# Breakout.net
KiCad netlist of a schematic drawn in Altium Designer
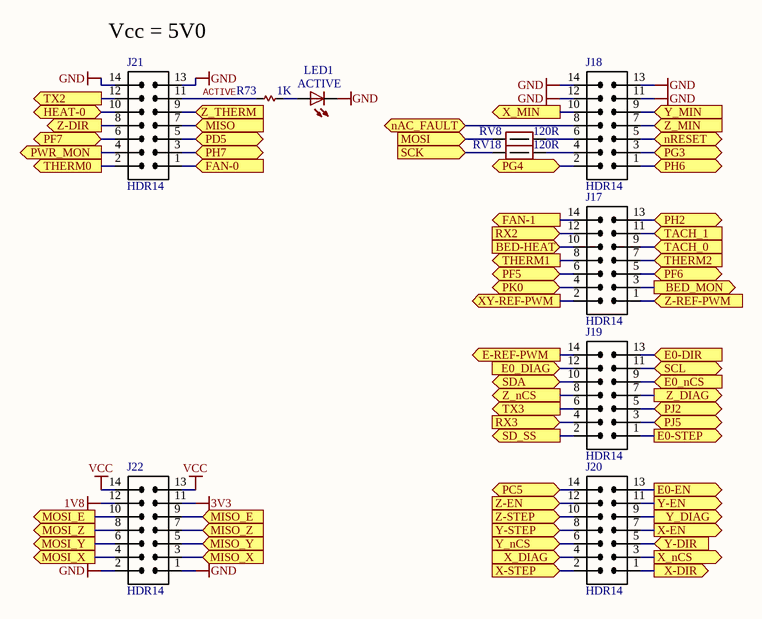
[diagram p0: Breakout.SchDoc]

(export (version "E")
  (design (tool "Eeschema 10.0.6"))
  (components
    (comp (ref "J17")
      (value "HDR14")
      (footprint "HDR2x7_SMT_BOT_ENTRY_EX")
      (description "CONN RCPT DUAL ENTRY 14POS .100\"")
      (fields (field (name "MANUFACTURER") "TE Connectivity") (field (name "TOLERANCE") "-NA-"))
      (libsource (lib "Connectors") (part "CONN 14PIN 0.1{dblquote} FEMALE 2-ROW SMT BOT-ENTRY_EX"))
    )
    (comp (ref "J18")
      (value "HDR14")
      (footprint "HDR2x7_SMT_BOT_ENTRY_EX")
      (description "CONN RCPT DUAL ENTRY 14POS .100\"")
      (fields (field (name "MANUFACTURER") "TE Connectivity") (field (name "TOLERANCE") "-NA-"))
      (libsource (lib "Connectors") (part "CONN 14PIN 0.1{dblquote} FEMALE 2-ROW SMT BOT-ENTRY_EX"))
    )
    (comp (ref "J19")
      (value "HDR14")
      (footprint "HDR2x7_SMT_BOT_ENTRY_EX")
      (description "CONN RCPT DUAL ENTRY 14POS .100\"")
      (fields (field (name "MANUFACTURER") "TE Connectivity") (field (name "TOLERANCE") "-NA-"))
      (libsource (lib "Connectors") (part "CONN 14PIN 0.1{dblquote} FEMALE 2-ROW SMT BOT-ENTRY_EX"))
    )
    (comp (ref "J20")
      (value "HDR14")
      (footprint "HDR2x7_SMT_BOT_ENTRY_EX")
      (description "CONN RCPT DUAL ENTRY 14POS .100\"")
      (fields (field (name "MANUFACTURER") "TE Connectivity") (field (name "TOLERANCE") "-NA-"))
      (libsource (lib "Connectors") (part "CONN 14PIN 0.1{dblquote} FEMALE 2-ROW SMT BOT-ENTRY_EX"))
    )
    (comp (ref "J21")
      (value "HDR14")
      (footprint "HDR2x7_SMT_BOT_ENTRY_EX")
      (description "CONN RCPT DUAL ENTRY 14POS .100\"")
      (fields (field (name "MANUFACTURER") "TE Connectivity") (field (name "TOLERANCE") "-NA-"))
      (libsource (lib "Connectors") (part "CONN 14PIN 0.1{dblquote} FEMALE 2-ROW SMT BOT-ENTRY_EX"))
    )
    (comp (ref "J22")
      (value "HDR14")
      (footprint "HDR2x7_SMT_BOT_ENTRY_EX")
      (description "CONN RCPT DUAL ENTRY 14POS .100\"")
      (fields (field (name "MANUFACTURER") "TE Connectivity") (field (name "TOLERANCE") "-NA-"))
      (libsource (lib "Connectors") (part "CONN 14PIN 0.1{dblquote} FEMALE 2-ROW SMT BOT-ENTRY_EX"))
    )
    (comp (ref "LED1")
      (value "YEL")
      (footprint "LED2012120")
      (description "LED 0805 Yellow")
      (fields (field (name "MANUFACTURER") "Dialight") (field (name "TOLERANCE") "NA"))
      (libsource (lib "3Delight") (part "5988140107F"))
    )
    (comp (ref "R73")
      (value "1K")
      (footprint "R0402")
      (description "RES SMD 1K OHM 1% 1/16W 0402")
      (fields (field (name "MANUFACTURER") "Yageo") (field (name "PART") "1k"))
      (libsource (lib "3Delight") (part "RC0402FR-071KL"))
    )
    (comp (ref "RV8")
      (value "120R")
      (footprint "R0402")
      (description "FERRITE BEAD 120 OHM 0402 1LN")
      (fields (field (name "MANUFACTURER") "Taiyo Yuden") (field (name "PART") "FERRITE 120R 1A 0402"))
      (libsource (lib "Inductors") (part "FERRITE 120R 1A 0402"))
    )
    (comp (ref "RV18")
      (value "120R")
      (footprint "R0402")
      (description "FERRITE BEAD 120 OHM 0402 1LN")
      (fields (field (name "MANUFACTURER") "Taiyo Yuden") (field (name "PART") "FERRITE 120R 1A 0402"))
      (libsource (lib "Inductors") (part "FERRITE 120R 1A 0402"))
    )
  )
  (nets
    (net (code "1") (name "/ACTIVE") (class "Default")
      (node (ref "J21") (pin "11") (pinfunction "S_11") (pintype "passive"))
      (node (ref "R73") (pin "2") (pinfunction "2_2") (pintype "passive"))
    )
    (net (code "2") (name "/BED-HEAT") (class "Default")
      (node (ref "J17") (pin "10") (pinfunction "S_10") (pintype "passive"))
    )
    (net (code "3") (name "/BED_MON") (class "Default")
      (node (ref "J17") (pin "3") (pinfunction "S_3") (pintype "passive"))
    )
    (net (code "4") (name "/E-REF-PWM") (class "Default")
      (node (ref "J19") (pin "14") (pinfunction "S_14") (pintype "passive"))
    )
    (net (code "5") (name "/E0-DIR") (class "Default")
      (node (ref "J19") (pin "13") (pinfunction "S_13") (pintype "passive"))
    )
    (net (code "6") (name "/E0-EN") (class "Default")
      (node (ref "J20") (pin "13") (pinfunction "S_13") (pintype "passive"))
    )
    (net (code "7") (name "/E0-STEP") (class "Default")
      (node (ref "J19") (pin "1") (pinfunction "S_1") (pintype "passive"))
    )
    (net (code "8") (name "/E0_DIAG") (class "Default")
      (node (ref "J19") (pin "12") (pinfunction "S_12") (pintype "passive"))
    )
    (net (code "9") (name "/E0_nCS") (class "Default")
      (node (ref "J19") (pin "9") (pinfunction "S_9") (pintype "passive"))
    )
    (net (code "10") (name "/FAN-0") (class "Default")
      (node (ref "J21") (pin "1") (pinfunction "S_1") (pintype "passive"))
    )
    (net (code "11") (name "/FAN-1") (class "Default")
      (node (ref "J17") (pin "14") (pinfunction "S_14") (pintype "passive"))
    )
    (net (code "12") (name "/HEAT-0") (class "Default")
      (node (ref "J21") (pin "10") (pinfunction "S_10") (pintype "passive"))
    )
    (net (code "13") (name "/MISO") (class "Default")
      (node (ref "J21") (pin "7") (pinfunction "S_7") (pintype "passive"))
    )
    (net (code "14") (name "/MISO_E") (class "Default")
      (node (ref "J22") (pin "9") (pinfunction "S_9") (pintype "passive"))
    )
    (net (code "15") (name "/MISO_X") (class "Default")
      (node (ref "J22") (pin "3") (pinfunction "S_3") (pintype "passive"))
    )
    (net (code "16") (name "/MISO_Y") (class "Default")
      (node (ref "J22") (pin "5") (pinfunction "S_5") (pintype "passive"))
    )
    (net (code "17") (name "/MISO_Z") (class "Default")
      (node (ref "J22") (pin "7") (pinfunction "S_7") (pintype "passive"))
    )
    (net (code "18") (name "/MOSI") (class "Default")
      (node (ref "RV8") (pin "2") (pinfunction "2_2") (pintype "passive"))
    )
    (net (code "19") (name "/MOSI_E") (class "Default")
      (node (ref "J22") (pin "10") (pinfunction "S_10") (pintype "passive"))
    )
    (net (code "20") (name "/MOSI_X") (class "Default")
      (node (ref "J22") (pin "4") (pinfunction "S_4") (pintype "passive"))
    )
    (net (code "21") (name "/MOSI_Y") (class "Default")
      (node (ref "J22") (pin "6") (pinfunction "S_6") (pintype "passive"))
    )
    (net (code "22") (name "/MOSI_Z") (class "Default")
      (node (ref "J22") (pin "8") (pinfunction "S_8") (pintype "passive"))
    )
    (net (code "23") (name "/PC5") (class "Default")
      (node (ref "J20") (pin "14") (pinfunction "S_14") (pintype "passive"))
    )
    (net (code "24") (name "/PD5") (class "Default")
      (node (ref "J21") (pin "5") (pinfunction "S_5") (pintype "passive"))
    )
    (net (code "25") (name "/PF5") (class "Default")
      (node (ref "J17") (pin "6") (pinfunction "S_6") (pintype "passive"))
    )
    (net (code "26") (name "/PF6") (class "Default")
      (node (ref "J17") (pin "5") (pinfunction "S_5") (pintype "passive"))
    )
    (net (code "27") (name "/PF7") (class "Default")
      (node (ref "J21") (pin "6") (pinfunction "S_6") (pintype "passive"))
    )
    (net (code "28") (name "/PG3") (class "Default")
      (node (ref "J18") (pin "3") (pinfunction "S_3") (pintype "passive"))
    )
    (net (code "29") (name "/PG4") (class "Default")
      (node (ref "J18") (pin "2") (pinfunction "S_2") (pintype "passive"))
    )
    (net (code "30") (name "/PH2") (class "Default")
      (node (ref "J17") (pin "13") (pinfunction "S_13") (pintype "passive"))
    )
    (net (code "31") (name "/PH6") (class "Default")
      (node (ref "J18") (pin "1") (pinfunction "S_1") (pintype "passive"))
    )
    (net (code "32") (name "/PH7") (class "Default")
      (node (ref "J21") (pin "3") (pinfunction "S_3") (pintype "passive"))
    )
    (net (code "33") (name "/PJ2") (class "Default")
      (node (ref "J19") (pin "5") (pinfunction "S_5") (pintype "passive"))
    )
    (net (code "34") (name "/PJ5") (class "Default")
      (node (ref "J19") (pin "3") (pinfunction "S_3") (pintype "passive"))
    )
    (net (code "35") (name "/PK0") (class "Default")
      (node (ref "J17") (pin "4") (pinfunction "S_4") (pintype "passive"))
    )
    (net (code "36") (name "/PWR_MON") (class "Default")
      (node (ref "J21") (pin "4") (pinfunction "S_4") (pintype "passive"))
    )
    (net (code "37") (name "/RX2") (class "Default")
      (node (ref "J17") (pin "12") (pinfunction "S_12") (pintype "passive"))
    )
    (net (code "38") (name "/RX3") (class "Default")
      (node (ref "J19") (pin "4") (pinfunction "S_4") (pintype "passive"))
    )
    (net (code "39") (name "/SCK") (class "Default")
      (node (ref "RV18") (pin "2") (pinfunction "2_2") (pintype "passive"))
    )
    (net (code "40") (name "/SCL") (class "Default")
      (node (ref "J19") (pin "11") (pinfunction "S_11") (pintype "passive"))
    )
    (net (code "41") (name "/SDA") (class "Default")
      (node (ref "J19") (pin "10") (pinfunction "S_10") (pintype "passive"))
    )
    (net (code "42") (name "/SD_SS") (class "Default")
      (node (ref "J19") (pin "2") (pinfunction "S_2") (pintype "passive"))
    )
    (net (code "43") (name "/TACH_0") (class "Default")
      (node (ref "J17") (pin "9") (pinfunction "S_9") (pintype "passive"))
    )
    (net (code "44") (name "/TACH_1") (class "Default")
      (node (ref "J17") (pin "11") (pinfunction "S_11") (pintype "passive"))
    )
    (net (code "45") (name "/THERM0") (class "Default")
      (node (ref "J21") (pin "2") (pinfunction "S_2") (pintype "passive"))
    )
    (net (code "46") (name "/THERM1") (class "Default")
      (node (ref "J17") (pin "8") (pinfunction "S_8") (pintype "passive"))
    )
    (net (code "47") (name "/THERM2") (class "Default")
      (node (ref "J17") (pin "7") (pinfunction "S_7") (pintype "passive"))
    )
    (net (code "48") (name "/TX2") (class "Default")
      (node (ref "J21") (pin "12") (pinfunction "S_12") (pintype "passive"))
    )
    (net (code "49") (name "/TX3") (class "Default")
      (node (ref "J19") (pin "6") (pinfunction "S_6") (pintype "passive"))
    )
    (net (code "50") (name "/X-DIR") (class "Default")
      (node (ref "J20") (pin "1") (pinfunction "S_1") (pintype "passive"))
    )
    (net (code "51") (name "/X-EN") (class "Default")
      (node (ref "J20") (pin "7") (pinfunction "S_7") (pintype "passive"))
    )
    (net (code "52") (name "/X-STEP") (class "Default")
      (node (ref "J20") (pin "2") (pinfunction "S_2") (pintype "passive"))
    )
    (net (code "53") (name "/XY-REF-PWM") (class "Default")
      (node (ref "J17") (pin "2") (pinfunction "S_2") (pintype "passive"))
    )
    (net (code "54") (name "/X_DIAG") (class "Default")
      (node (ref "J20") (pin "4") (pinfunction "S_4") (pintype "passive"))
    )
    (net (code "55") (name "/X_MIN") (class "Default")
      (node (ref "J18") (pin "10") (pinfunction "S_10") (pintype "passive"))
    )
    (net (code "56") (name "/X_nCS") (class "Default")
      (node (ref "J20") (pin "3") (pinfunction "S_3") (pintype "passive"))
    )
    (net (code "57") (name "/Y-DIR") (class "Default")
      (node (ref "J20") (pin "5") (pinfunction "S_5") (pintype "passive"))
    )
    (net (code "58") (name "/Y-EN") (class "Default")
      (node (ref "J20") (pin "11") (pinfunction "S_11") (pintype "passive"))
    )
    (net (code "59") (name "/Y-STEP") (class "Default")
      (node (ref "J20") (pin "8") (pinfunction "S_8") (pintype "passive"))
    )
    (net (code "60") (name "/Y_DIAG") (class "Default")
      (node (ref "J20") (pin "9") (pinfunction "S_9") (pintype "passive"))
    )
    (net (code "61") (name "/Y_MIN") (class "Default")
      (node (ref "J18") (pin "9") (pinfunction "S_9") (pintype "passive"))
    )
    (net (code "62") (name "/Y_nCS") (class "Default")
      (node (ref "J20") (pin "6") (pinfunction "S_6") (pintype "passive"))
    )
    (net (code "63") (name "/Z-DIR") (class "Default")
      (node (ref "J21") (pin "8") (pinfunction "S_8") (pintype "passive"))
    )
    (net (code "64") (name "/Z-EN") (class "Default")
      (node (ref "J20") (pin "12") (pinfunction "S_12") (pintype "passive"))
    )
    (net (code "65") (name "/Z-REF-PWM") (class "Default")
      (node (ref "J17") (pin "1") (pinfunction "S_1") (pintype "passive"))
    )
    (net (code "66") (name "/Z-STEP") (class "Default")
      (node (ref "J20") (pin "10") (pinfunction "S_10") (pintype "passive"))
    )
    (net (code "67") (name "/Z_DIAG") (class "Default")
      (node (ref "J19") (pin "7") (pinfunction "S_7") (pintype "passive"))
    )
    (net (code "68") (name "/Z_MIN") (class "Default")
      (node (ref "J18") (pin "7") (pinfunction "S_7") (pintype "passive"))
    )
    (net (code "69") (name "/Z_THERM") (class "Default")
      (node (ref "J21") (pin "9") (pinfunction "S_9") (pintype "passive"))
    )
    (net (code "70") (name "/Z_nCS") (class "Default")
      (node (ref "J19") (pin "8") (pinfunction "S_8") (pintype "passive"))
    )
    (net (code "71") (name "/nAC_FAULT") (class "Default")
      (node (ref "J18") (pin "8") (pinfunction "S_8") (pintype "passive"))
    )
    (net (code "72") (name "/nRESET") (class "Default")
      (node (ref "J18") (pin "5") (pinfunction "S_5") (pintype "passive"))
    )
    (net (code "73") (name "1V8") (class "Default")
      (node (ref "J22") (pin "12") (pinfunction "S_12") (pintype "passive"))
    )
    (net (code "74") (name "3V3") (class "Default")
      (node (ref "J22") (pin "11") (pinfunction "S_11") (pintype "passive"))
    )
    (net (code "75") (name "GND") (class "Default")
      (node (ref "J18") (pin "11") (pinfunction "S_11") (pintype "passive"))
      (node (ref "J18") (pin "12") (pinfunction "S_12") (pintype "passive"))
      (node (ref "J18") (pin "13") (pinfunction "S_13") (pintype "passive"))
      (node (ref "J18") (pin "14") (pinfunction "S_14") (pintype "passive"))
      (node (ref "J21") (pin "13") (pinfunction "S_13") (pintype "passive"))
      (node (ref "J21") (pin "14") (pinfunction "S_14") (pintype "passive"))
      (node (ref "J22") (pin "1") (pinfunction "S_1") (pintype "passive"))
      (node (ref "J22") (pin "2") (pinfunction "S_2") (pintype "passive"))
      (node (ref "LED1") (pin "C") (pinfunction "C_C") (pintype "passive"))
    )
    (net (code "76") (name "Net-(J18-S-Pad4)") (class "Default")
      (node (ref "J18") (pin "4") (pinfunction "S_4") (pintype "passive"))
      (node (ref "RV18") (pin "1") (pinfunction "1_1") (pintype "passive"))
    )
    (net (code "77") (name "Net-(J18-S-Pad6)") (class "Default")
      (node (ref "J18") (pin "6") (pinfunction "S_6") (pintype "passive"))
      (node (ref "RV8") (pin "1") (pinfunction "1_1") (pintype "passive"))
    )
    (net (code "78") (name "Net-(LED1-PadA)") (class "Default")
      (node (ref "LED1") (pin "A") (pinfunction "A_A") (pintype "passive"))
      (node (ref "R73") (pin "1") (pinfunction "1_1") (pintype "passive"))
    )
    (net (code "79") (name "VCC") (class "Default")
      (node (ref "J22") (pin "13") (pinfunction "S_13") (pintype "passive"))
      (node (ref "J22") (pin "14") (pinfunction "S_14") (pintype "passive"))
    )
  )
)
